# irkit_periph_lightFilter_v03.net
KiCad netlist of a schematic drawn in EAGLE
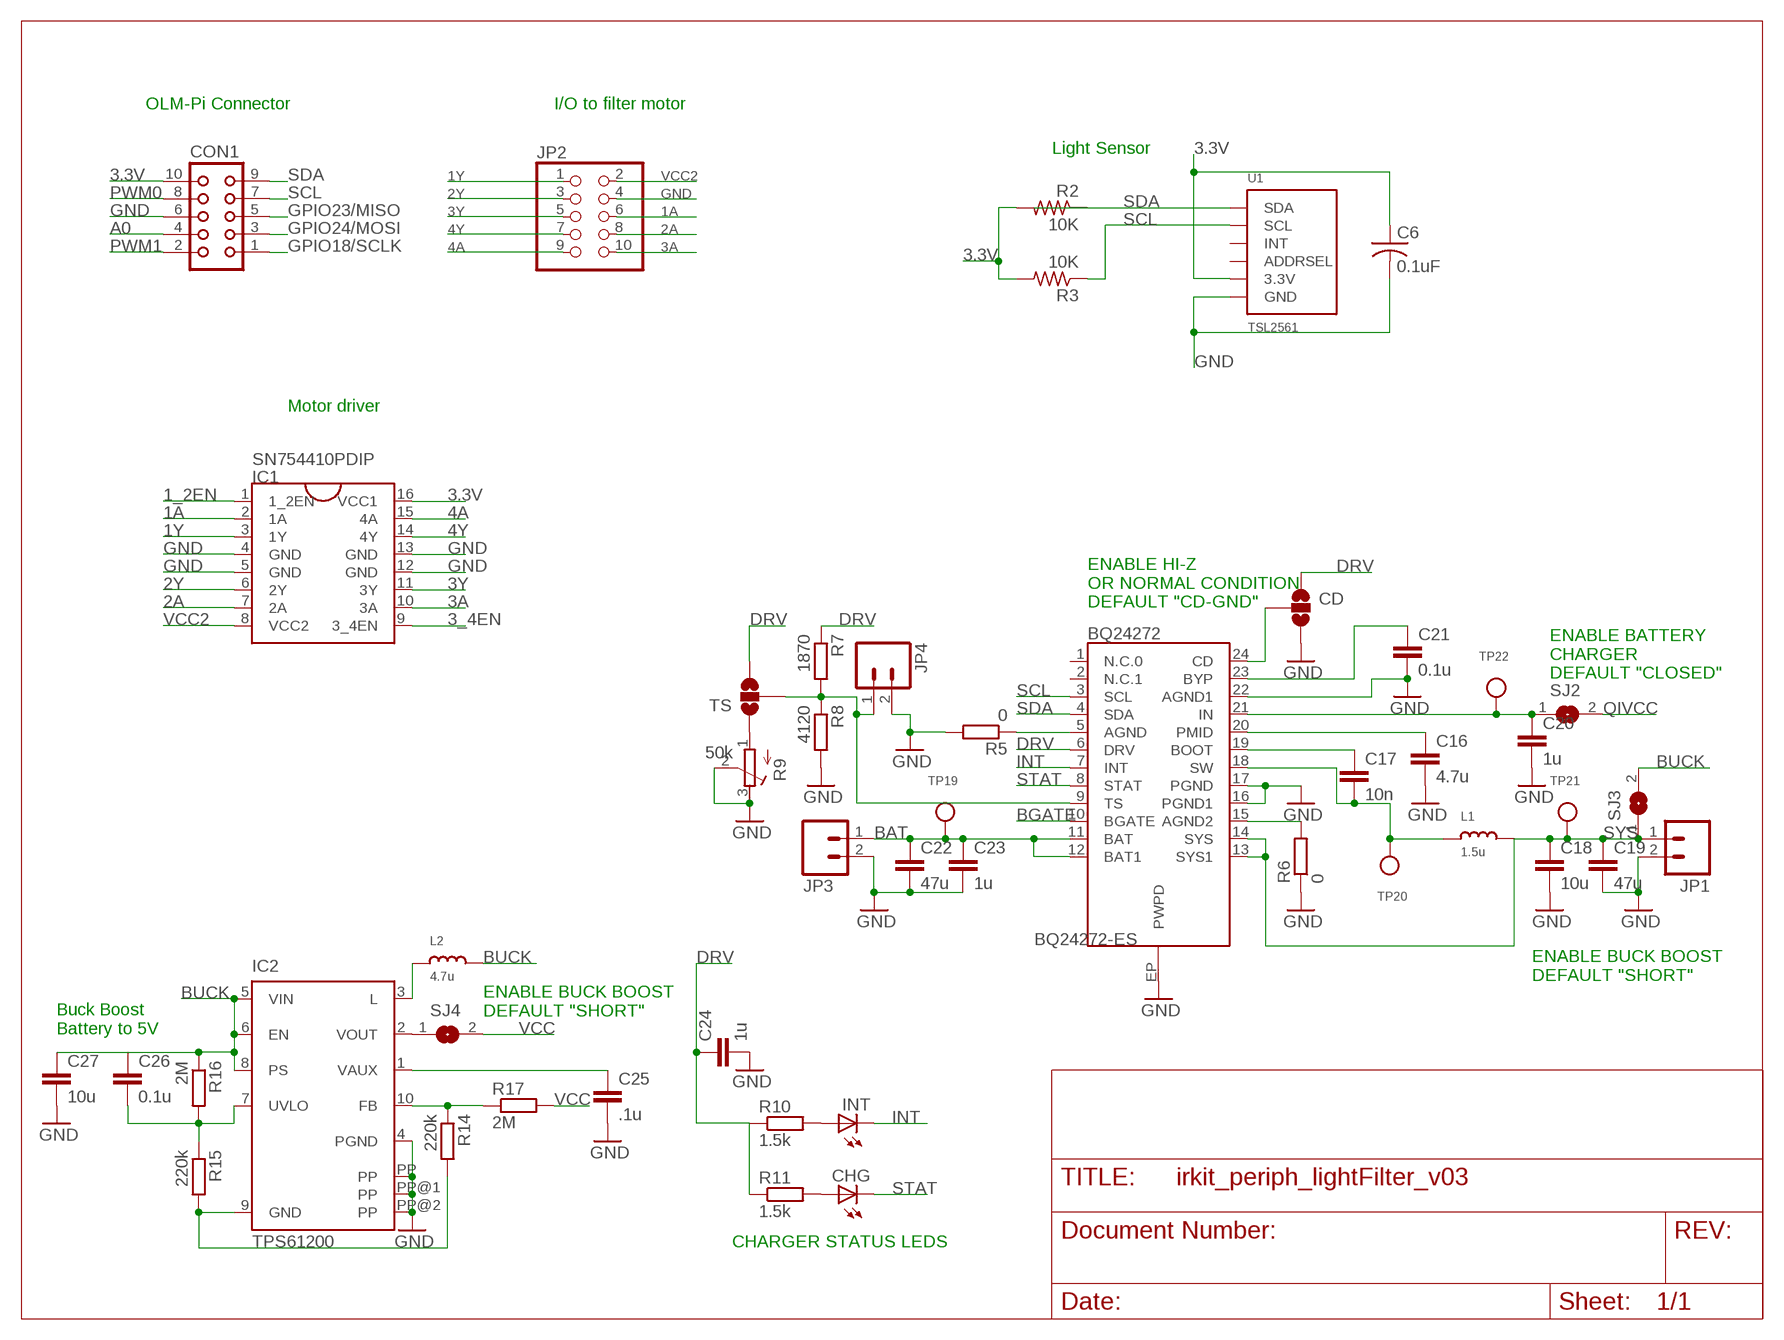
[diagram p0: schematic, sheet 1]

(export (version "E")
  (design (tool "Eeschema 10.0.6"))
  (components
    (comp (ref "BQ24272")
      (value "BQ24272-ES")
      (footprint "eagle-import:QFN-24_ALT2")
      (libsource (lib "eagle-import") (part "BQ24272-ES"))
    )
    (comp (ref "C6")
      (value "0.1uF")
      (footprint "eagle-import:C0805")
      (libsource (lib "eagle-import") (part "C-USC0805"))
    )
    (comp (ref "C16")
      (value "4.7u")
      (footprint "eagle-import:C0603K")
      (libsource (lib "eagle-import") (part "C-EUC0603K"))
    )
    (comp (ref "C17")
      (value "10n")
      (footprint "eagle-import:C0603K")
      (libsource (lib "eagle-import") (part "C-EUC0603K"))
    )
    (comp (ref "C18")
      (value "10u")
      (footprint "eagle-import:C0603K")
      (libsource (lib "eagle-import") (part "C-EUC0603K"))
    )
    (comp (ref "C19")
      (value "47u")
      (footprint "eagle-import:C0603K")
      (libsource (lib "eagle-import") (part "C-EUC0603K"))
    )
    (comp (ref "C20")
      (value "1u")
      (footprint "eagle-import:C0603K")
      (libsource (lib "eagle-import") (part "C-EUC0603K"))
    )
    (comp (ref "C21")
      (value "0.1u")
      (footprint "eagle-import:C0603K")
      (libsource (lib "eagle-import") (part "C-EUC0603K"))
    )
    (comp (ref "C22")
      (value "47u")
      (footprint "eagle-import:C0603K")
      (libsource (lib "eagle-import") (part "C-EUC0603K"))
    )
    (comp (ref "C23")
      (value "1u")
      (footprint "eagle-import:C0603K")
      (libsource (lib "eagle-import") (part "C-EUC0603K"))
    )
    (comp (ref "C24")
      (value "1u")
      (footprint "eagle-import:C0603K")
      (libsource (lib "eagle-import") (part "C-EUC0603K"))
    )
    (comp (ref "C25")
      (value ".1u")
      (footprint "eagle-import:C0603K")
      (libsource (lib "eagle-import") (part "C-EUC0603K"))
    )
    (comp (ref "C26")
      (value "0.1u")
      (footprint "eagle-import:C0603K")
      (libsource (lib "eagle-import") (part "C-EUC0603K"))
    )
    (comp (ref "C27")
      (value "10u")
      (footprint "eagle-import:C0603K")
      (libsource (lib "eagle-import") (part "C-EUC0603K"))
    )
    (comp (ref "CD")
      (value "SOLDERJUMPER_2WAYS")
      (footprint "eagle-import:SJ_3")
      (libsource (lib "eagle-import") (part "SOLDERJUMPER_2WAYS"))
    )
    (comp (ref "CHG")
      (value "LEDCHIP-LED0603")
      (footprint "eagle-import:CHIP-LED0603")
      (libsource (lib "eagle-import") (part "LEDCHIP-LED0603"))
    )
    (comp (ref "CON1")
      (value "CON10L")
      (footprint "eagle-import:CON10L")
      (libsource (lib "eagle-import") (part "CON10L"))
    )
    (comp (ref "IC1")
      (value "SN754410PDIP")
      (footprint "eagle-import:DIL16")
      (libsource (lib "eagle-import") (part "SN754410PDIP"))
    )
    (comp (ref "IC2")
      (value "TPS61200")
      (footprint "eagle-import:S-PDSO-N10")
      (fields (field (name "MPN") "TPS61200DRCT"))
      (libsource (lib "eagle-import") (part "TPS61200"))
    )
    (comp (ref "INT")
      (value "LEDCHIP-LED0603")
      (footprint "eagle-import:CHIP-LED0603")
      (libsource (lib "eagle-import") (part "LEDCHIP-LED0603"))
    )
    (comp (ref "JP1")
      (value "M02PTH3")
      (footprint "eagle-import:1X02_LONGPADS")
      (libsource (lib "eagle-import") (part "M02PTH3"))
    )
    (comp (ref "JP2")
      (value "PINHD-2X5")
      (footprint "eagle-import:2X05")
      (libsource (lib "eagle-import") (part "PINHD-2X5"))
    )
    (comp (ref "JP3")
      (value "M02PTH3")
      (footprint "eagle-import:1X02_LONGPADS")
      (libsource (lib "eagle-import") (part "M02PTH3"))
    )
    (comp (ref "JP4")
      (value "M02PTH3")
      (footprint "eagle-import:1X02_LONGPADS")
      (libsource (lib "eagle-import") (part "M02PTH3"))
    )
    (comp (ref "L1")
      (value "1.5u")
      (footprint "eagle-import:INDUCTOR_5X5MM_NR5040_NOTHERMALS")
      (libsource (lib "eagle-import") (part "INDUCTORNR5040"))
    )
    (comp (ref "L2")
      (value "4.7u")
      (footprint "eagle-import:INDUCTOR_5X5MM_NR5040_NOTHERMALS")
      (libsource (lib "eagle-import") (part "INDUCTORNR5040"))
    )
    (comp (ref "R2")
      (value "10K")
      (footprint "eagle-import:R0805")
      (libsource (lib "eagle-import") (part "R-US_R0805"))
    )
    (comp (ref "R3")
      (value "10K")
      (footprint "eagle-import:R0805")
      (libsource (lib "eagle-import") (part "R-US_R0805"))
    )
    (comp (ref "R5")
      (value "0")
      (footprint "eagle-import:R0402")
      (fields (field (name "MPN") "ERJ3EKF3000V"))
      (libsource (lib "eagle-import") (part "R-EU_R0402"))
    )
    (comp (ref "R6")
      (value "0")
      (footprint "eagle-import:R0402")
      (fields (field (name "MPN") "ERJ3EKF3000V"))
      (libsource (lib "eagle-import") (part "R-EU_R0402"))
    )
    (comp (ref "R7")
      (value "1870")
      (footprint "eagle-import:R0402")
      (fields (field (name "MPN") "ERJ3EKF3000V"))
      (libsource (lib "eagle-import") (part "R-EU_R0402"))
    )
    (comp (ref "R8")
      (value "4120")
      (footprint "eagle-import:R0402")
      (fields (field (name "MPN") "ERJ3EKF3000V"))
      (libsource (lib "eagle-import") (part "R-EU_R0402"))
    )
    (comp (ref "R9")
      (value "50k")
      (footprint "eagle-import:RTRIM64Y")
      (libsource (lib "eagle-import") (part "R-TRIMM64Y"))
    )
    (comp (ref "R10")
      (value "1.5k")
      (footprint "eagle-import:R0402")
      (fields (field (name "MPN") "ERJ3EKF3000V"))
      (libsource (lib "eagle-import") (part "R-EU_R0402"))
    )
    (comp (ref "R11")
      (value "1.5k")
      (footprint "eagle-import:R0402")
      (fields (field (name "MPN") "ERJ3EKF3000V"))
      (libsource (lib "eagle-import") (part "R-EU_R0402"))
    )
    (comp (ref "R14")
      (value "220k")
      (footprint "eagle-import:R0402")
      (fields (field (name "MPN") "ERJ3EKF3000V"))
      (libsource (lib "eagle-import") (part "R-EU_R0402"))
    )
    (comp (ref "R15")
      (value "220k")
      (footprint "eagle-import:R0402")
      (fields (field (name "MPN") "ERJ3EKF3000V"))
      (libsource (lib "eagle-import") (part "R-EU_R0402"))
    )
    (comp (ref "R16")
      (value "2M")
      (footprint "eagle-import:R0402")
      (fields (field (name "MPN") "ERJ3EKF3000V"))
      (libsource (lib "eagle-import") (part "R-EU_R0402"))
    )
    (comp (ref "R17")
      (value "2M")
      (footprint "eagle-import:R0402")
      (fields (field (name "MPN") "ERJ3EKF3000V"))
      (libsource (lib "eagle-import") (part "R-EU_R0402"))
    )
    (comp (ref "SJ2") (value "SJ") (footprint "eagle-import:SJ") (libsource (lib "eagle-import") (part "SJ")))
    (comp (ref "SJ3") (value "SJ") (footprint "eagle-import:SJ") (libsource (lib "eagle-import") (part "SJ")))
    (comp (ref "SJ4") (value "SJ") (footprint "eagle-import:SJ") (libsource (lib "eagle-import") (part "SJ")))
    (comp (ref "TP19")
      (value "TESTPOINTROUND1MM")
      (footprint "eagle-import:TESTPOINT_ROUND_1MM")
      (libsource (lib "eagle-import") (part "TESTPOINTROUND1MM"))
    )
    (comp (ref "TP20")
      (value "TESTPOINTROUND1MM")
      (footprint "eagle-import:TESTPOINT_ROUND_1MM")
      (libsource (lib "eagle-import") (part "TESTPOINTROUND1MM"))
    )
    (comp (ref "TP21")
      (value "TESTPOINTROUND1MM")
      (footprint "eagle-import:TESTPOINT_ROUND_1MM")
      (libsource (lib "eagle-import") (part "TESTPOINTROUND1MM"))
    )
    (comp (ref "TP22")
      (value "TESTPOINTROUND1MM")
      (footprint "eagle-import:TESTPOINT_ROUND_1MM")
      (libsource (lib "eagle-import") (part "TESTPOINTROUND1MM"))
    )
    (comp (ref "TS")
      (value "SOLDERJUMPER_2WAYS")
      (footprint "eagle-import:SJ_3")
      (libsource (lib "eagle-import") (part "SOLDERJUMPER_2WAYS"))
    )
    (comp (ref "U1")
      (value "TSL2561")
      (footprint "eagle-import:TSL2561_FN")
      (libsource (lib "eagle-import") (part "TSL2561"))
    )
  )
  (nets
    (net (code "1") (name "/1A") (class "Default")
      (node (ref "IC1") (pin "2") (pinfunction "1A_2") (pintype "bidirectional"))
      (node (ref "JP2") (pin "6") (pinfunction "6_6") (pintype "passive"))
    )
    (net (code "2") (name "/1Y") (class "Default")
      (node (ref "IC1") (pin "3") (pinfunction "1Y_3") (pintype "bidirectional"))
      (node (ref "JP2") (pin "1") (pinfunction "1_1") (pintype "passive"))
    )
    (net (code "3") (name "/1_2EN") (class "Default")
      (node (ref "IC1") (pin "1") (pinfunction "1_2EN_1") (pintype "bidirectional"))
    )
    (net (code "4") (name "/2A") (class "Default")
      (node (ref "IC1") (pin "7") (pinfunction "2A_7") (pintype "bidirectional"))
      (node (ref "JP2") (pin "8") (pinfunction "8_8") (pintype "passive"))
    )
    (net (code "5") (name "/2Y") (class "Default")
      (node (ref "IC1") (pin "6") (pinfunction "2Y_6") (pintype "bidirectional"))
      (node (ref "JP2") (pin "3") (pinfunction "3_3") (pintype "passive"))
    )
    (net (code "6") (name "/3.3V") (class "Default")
      (node (ref "C6") (pin "1") (pinfunction "1_1") (pintype "passive"))
      (node (ref "CON1") (pin "10") (pinfunction "10_10") (pintype "passive"))
      (node (ref "IC1") (pin "16") (pinfunction "VCC1_16") (pintype "bidirectional"))
      (node (ref "R2") (pin "2") (pinfunction "2_2") (pintype "passive"))
      (node (ref "R3") (pin "2") (pinfunction "2_2") (pintype "passive"))
      (node (ref "U1") (pin "VDD") (pinfunction "3.3V_VDD") (pintype "bidirectional"))
    )
    (net (code "7") (name "/3A") (class "Default")
      (node (ref "IC1") (pin "10") (pinfunction "3A_10") (pintype "bidirectional"))
      (node (ref "JP2") (pin "10") (pinfunction "10_10") (pintype "passive"))
    )
    (net (code "8") (name "/3Y") (class "Default")
      (node (ref "IC1") (pin "11") (pinfunction "3Y_11") (pintype "bidirectional"))
      (node (ref "JP2") (pin "5") (pinfunction "5_5") (pintype "passive"))
    )
    (net (code "9") (name "/3_4EN") (class "Default")
      (node (ref "IC1") (pin "9") (pinfunction "3_4EN_9") (pintype "bidirectional"))
    )
    (net (code "10") (name "/4A") (class "Default")
      (node (ref "IC1") (pin "15") (pinfunction "4A_15") (pintype "bidirectional"))
      (node (ref "JP2") (pin "9") (pinfunction "9_9") (pintype "passive"))
    )
    (net (code "11") (name "/4Y") (class "Default")
      (node (ref "IC1") (pin "14") (pinfunction "4Y_14") (pintype "bidirectional"))
      (node (ref "JP2") (pin "7") (pinfunction "7_7") (pintype "passive"))
    )
    (net (code "12") (name "/A0") (class "Default")
      (node (ref "CON1") (pin "4") (pinfunction "4_4") (pintype "passive"))
    )
    (net (code "13") (name "/BAT") (class "Default")
      (node (ref "BQ24272") (pin "11") (pinfunction "BAT_11") (pintype "bidirectional"))
      (node (ref "BQ24272") (pin "12") (pinfunction "BAT1_12") (pintype "bidirectional"))
      (node (ref "C22") (pin "1") (pinfunction "1_1") (pintype "passive"))
      (node (ref "C23") (pin "1") (pinfunction "1_1") (pintype "passive"))
      (node (ref "JP3") (pin "1") (pinfunction "1_1") (pintype "passive"))
      (node (ref "TP19") (pin "P$1") (pinfunction "P$1_P$1") (pintype "bidirectional"))
    )
    (net (code "14") (name "/BGATE") (class "Default")
      (node (ref "BQ24272") (pin "10") (pinfunction "BGATE_10") (pintype "bidirectional"))
    )
    (net (code "15") (name "/BUCK") (class "Default")
      (node (ref "C26") (pin "1") (pinfunction "1_1") (pintype "passive"))
      (node (ref "C27") (pin "1") (pinfunction "1_1") (pintype "passive"))
      (node (ref "IC2") (pin "5") (pinfunction "VIN_5") (pintype "input"))
      (node (ref "IC2") (pin "6") (pinfunction "EN_6") (pintype "input"))
      (node (ref "IC2") (pin "8") (pinfunction "PS_8") (pintype "input"))
      (node (ref "L2") (pin "P$2") (pinfunction "2_P$2") (pintype "passive"))
      (node (ref "R16") (pin "1") (pinfunction "1_1") (pintype "passive"))
      (node (ref "SJ3") (pin "2") (pinfunction "2_2") (pintype "passive"))
    )
    (net (code "16") (name "/DRV") (class "Default")
      (node (ref "BQ24272") (pin "6") (pinfunction "DRV_6") (pintype "bidirectional"))
      (node (ref "C24") (pin "1") (pinfunction "1_1") (pintype "passive"))
      (node (ref "CD") (pin "1") (pinfunction "1_1") (pintype "passive"))
      (node (ref "R10") (pin "1") (pinfunction "1_1") (pintype "passive"))
      (node (ref "R11") (pin "1") (pinfunction "1_1") (pintype "passive"))
      (node (ref "R7") (pin "1") (pinfunction "1_1") (pintype "passive"))
      (node (ref "TS") (pin "3") (pinfunction "3_3") (pintype "passive"))
    )
    (net (code "17") (name "/GPIO18{slash}SCLK") (class "Default")
      (node (ref "CON1") (pin "1") (pinfunction "1_1") (pintype "passive"))
    )
    (net (code "18") (name "/GPIO23{slash}MISO") (class "Default")
      (node (ref "CON1") (pin "5") (pinfunction "5_5") (pintype "passive"))
    )
    (net (code "19") (name "/GPIO24{slash}MOSI") (class "Default")
      (node (ref "CON1") (pin "3") (pinfunction "3_3") (pintype "passive"))
    )
    (net (code "20") (name "/INT") (class "Default")
      (node (ref "BQ24272") (pin "7") (pinfunction "INT_7") (pintype "bidirectional"))
      (node (ref "INT") (pin "C") (pinfunction "C_C") (pintype "passive"))
    )
    (net (code "21") (name "/PWM0") (class "Default")
      (node (ref "CON1") (pin "8") (pinfunction "8_8") (pintype "passive"))
    )
    (net (code "22") (name "/PWM1") (class "Default")
      (node (ref "CON1") (pin "2") (pinfunction "2_2") (pintype "passive"))
    )
    (net (code "23") (name "/QIVCC") (class "Default")
      (node (ref "SJ2") (pin "2") (pinfunction "2_2") (pintype "passive"))
    )
    (net (code "24") (name "/SCL") (class "Default")
      (node (ref "BQ24272") (pin "3") (pinfunction "SCL_3") (pintype "bidirectional"))
      (node (ref "CON1") (pin "7") (pinfunction "7_7") (pintype "passive"))
      (node (ref "R3") (pin "1") (pinfunction "1_1") (pintype "passive"))
      (node (ref "U1") (pin "CLK") (pinfunction "SCL_CLK") (pintype "bidirectional"))
    )
    (net (code "25") (name "/SDA") (class "Default")
      (node (ref "BQ24272") (pin "4") (pinfunction "SDA_4") (pintype "bidirectional"))
      (node (ref "CON1") (pin "9") (pinfunction "9_9") (pintype "passive"))
      (node (ref "R2") (pin "1") (pinfunction "1_1") (pintype "passive"))
      (node (ref "U1") (pin "DATA") (pinfunction "SDA_DATA") (pintype "bidirectional"))
    )
    (net (code "26") (name "/STAT") (class "Default")
      (node (ref "BQ24272") (pin "8") (pinfunction "STAT_8") (pintype "bidirectional"))
      (node (ref "CHG") (pin "C") (pinfunction "C_C") (pintype "passive"))
    )
    (net (code "27") (name "/SYS") (class "Default")
      (node (ref "BQ24272") (pin "13") (pinfunction "SYS1_13") (pintype "bidirectional"))
      (node (ref "BQ24272") (pin "14") (pinfunction "SYS_14") (pintype "bidirectional"))
      (node (ref "C18") (pin "1") (pinfunction "1_1") (pintype "passive"))
      (node (ref "C19") (pin "1") (pinfunction "1_1") (pintype "passive"))
      (node (ref "JP1") (pin "1") (pinfunction "1_1") (pintype "passive"))
      (node (ref "L1") (pin "P$2") (pinfunction "2_P$2") (pintype "passive"))
      (node (ref "SJ3") (pin "1") (pinfunction "1_1") (pintype "passive"))
      (node (ref "TP21") (pin "P$1") (pinfunction "P$1_P$1") (pintype "bidirectional"))
    )
    (net (code "28") (name "/VCC") (class "Default")
      (node (ref "R17") (pin "2") (pinfunction "2_2") (pintype "passive"))
      (node (ref "SJ4") (pin "2") (pinfunction "2_2") (pintype "passive"))
    )
    (net (code "29") (name "/VCC2") (class "Default")
      (node (ref "IC1") (pin "8") (pinfunction "VCC2_8") (pintype "bidirectional"))
      (node (ref "JP2") (pin "2") (pinfunction "2_2") (pintype "passive"))
    )
    (net (code "30") (name "GND") (class "Default")
      (node (ref "BQ24272") (pin "16") (pinfunction "PGND1_16") (pintype "bidirectional"))
      (node (ref "BQ24272") (pin "17") (pinfunction "PGND_17") (pintype "bidirectional"))
      (node (ref "BQ24272") (pin "22") (pinfunction "AGND1_22") (pintype "bidirectional"))
      (node (ref "BQ24272") (pin "EP") (pinfunction "PWPD_EP") (pintype "bidirectional"))
      (node (ref "C16") (pin "2") (pinfunction "2_2") (pintype "passive"))
      (node (ref "C18") (pin "2") (pinfunction "2_2") (pintype "passive"))
      (node (ref "C19") (pin "2") (pinfunction "2_2") (pintype "passive"))
      (node (ref "C20") (pin "2") (pinfunction "2_2") (pintype "passive"))
      (node (ref "C21") (pin "2") (pinfunction "2_2") (pintype "passive"))
      (node (ref "C22") (pin "2") (pinfunction "2_2") (pintype "passive"))
      (node (ref "C23") (pin "2") (pinfunction "2_2") (pintype "passive"))
      (node (ref "C24") (pin "2") (pinfunction "2_2") (pintype "passive"))
      (node (ref "C25") (pin "2") (pinfunction "2_2") (pintype "passive"))
      (node (ref "C27") (pin "2") (pinfunction "2_2") (pintype "passive"))
      (node (ref "C6") (pin "2") (pinfunction "2_2") (pintype "passive"))
      (node (ref "CD") (pin "3") (pinfunction "3_3") (pintype "passive"))
      (node (ref "CON1") (pin "6") (pinfunction "6_6") (pintype "passive"))
      (node (ref "IC1") (pin "12") (pinfunction "GND_12") (pintype "bidirectional"))
      (node (ref "IC1") (pin "13") (pinfunction "GND_13") (pintype "bidirectional"))
      (node (ref "IC1") (pin "4") (pinfunction "GND_4") (pintype "bidirectional"))
      (node (ref "IC1") (pin "5") (pinfunction "GND_5") (pintype "bidirectional"))
      (node (ref "IC2") (pin "4") (pinfunction "PGND_4") (pintype "power_in"))
      (node (ref "IC2") (pin "PP") (pinfunction "PP_PP") (pintype "power_in"))
      (node (ref "IC2") (pin "PP@1") (pinfunction "PP_PP@1") (pintype "power_in"))
      (node (ref "IC2") (pin "PP@2") (pinfunction "PP_PP@2") (pintype "power_in"))
      (node (ref "JP1") (pin "2") (pinfunction "2_2") (pintype "passive"))
      (node (ref "JP2") (pin "4") (pinfunction "4_4") (pintype "passive"))
      (node (ref "JP3") (pin "2") (pinfunction "2_2") (pintype "passive"))
      (node (ref "JP4") (pin "2") (pinfunction "2_2") (pintype "passive"))
      (node (ref "R5") (pin "2") (pinfunction "2_2") (pintype "passive"))
      (node (ref "R6") (pin "1") (pinfunction "1_1") (pintype "passive"))
      (node (ref "R8") (pin "2") (pinfunction "2_2") (pintype "passive"))
      (node (ref "R9") (pin "2") (pinfunction "S_2") (pintype "passive"))
      (node (ref "R9") (pin "3") (pinfunction "E_3") (pintype "passive"))
      (node (ref "U1") (pin "VSS") (pinfunction "GND_VSS") (pintype "bidirectional"))
    )
    (net (code "31") (name "Net-(BQ24272-AGND)") (class "Default")
      (node (ref "BQ24272") (pin "5") (pinfunction "AGND_5") (pintype "bidirectional"))
      (node (ref "R5") (pin "1") (pinfunction "1_1") (pintype "passive"))
    )
    (net (code "32") (name "Net-(BQ24272-AGND2)") (class "Default")
      (node (ref "BQ24272") (pin "15") (pinfunction "AGND2_15") (pintype "bidirectional"))
      (node (ref "R6") (pin "2") (pinfunction "2_2") (pintype "passive"))
    )
    (net (code "33") (name "Net-(BQ24272-BOOT)") (class "Default")
      (node (ref "BQ24272") (pin "19") (pinfunction "BOOT_19") (pintype "bidirectional"))
      (node (ref "C17") (pin "1") (pinfunction "1_1") (pintype "passive"))
    )
    (net (code "34") (name "Net-(BQ24272-BYP)") (class "Default")
      (node (ref "BQ24272") (pin "23") (pinfunction "BYP_23") (pintype "bidirectional"))
      (node (ref "C21") (pin "1") (pinfunction "1_1") (pintype "passive"))
    )
    (net (code "35") (name "Net-(BQ24272-CD)") (class "Default")
      (node (ref "BQ24272") (pin "24") (pinfunction "CD_24") (pintype "bidirectional"))
      (node (ref "CD") (pin "2") (pinfunction "2_2") (pintype "passive"))
    )
    (net (code "36") (name "Net-(BQ24272-IN)") (class "Default")
      (node (ref "BQ24272") (pin "21") (pinfunction "IN_21") (pintype "bidirectional"))
      (node (ref "C20") (pin "1") (pinfunction "1_1") (pintype "passive"))
      (node (ref "SJ2") (pin "1") (pinfunction "1_1") (pintype "passive"))
      (node (ref "TP22") (pin "P$1") (pinfunction "P$1_P$1") (pintype "bidirectional"))
    )
    (net (code "37") (name "Net-(BQ24272-PMID)") (class "Default")
      (node (ref "BQ24272") (pin "20") (pinfunction "PMID_20") (pintype "bidirectional"))
      (node (ref "C16") (pin "1") (pinfunction "1_1") (pintype "passive"))
    )
    (net (code "38") (name "Net-(BQ24272-SW)") (class "Default")
      (node (ref "BQ24272") (pin "18") (pinfunction "SW_18") (pintype "bidirectional"))
      (node (ref "C17") (pin "2") (pinfunction "2_2") (pintype "passive"))
      (node (ref "L1") (pin "P$1") (pinfunction "1_P$1") (pintype "passive"))
      (node (ref "TP20") (pin "P$1") (pinfunction "P$1_P$1") (pintype "bidirectional"))
    )
    (net (code "39") (name "Net-(BQ24272-TS)") (class "Default")
      (node (ref "BQ24272") (pin "9") (pinfunction "TS_9") (pintype "bidirectional"))
      (node (ref "JP4") (pin "1") (pinfunction "1_1") (pintype "passive"))
      (node (ref "R7") (pin "2") (pinfunction "2_2") (pintype "passive"))
      (node (ref "R8") (pin "1") (pinfunction "1_1") (pintype "passive"))
      (node (ref "TS") (pin "2") (pinfunction "2_2") (pintype "passive"))
    )
    (net (code "40") (name "Net-(CHG-PadA)") (class "Default")
      (node (ref "CHG") (pin "A") (pinfunction "A_A") (pintype "passive"))
      (node (ref "R11") (pin "2") (pinfunction "2_2") (pintype "passive"))
    )
    (net (code "41") (name "Net-(IC2-FB)") (class "Default")
      (node (ref "IC2") (pin "10") (pinfunction "FB_10") (pintype "input"))
      (node (ref "R14") (pin "1") (pinfunction "1_1") (pintype "passive"))
      (node (ref "R17") (pin "1") (pinfunction "1_1") (pintype "passive"))
    )
    (net (code "42") (name "Net-(IC2-GND)") (class "Default")
      (node (ref "IC2") (pin "9") (pinfunction "GND_9") (pintype "power_in"))
      (node (ref "R14") (pin "2") (pinfunction "2_2") (pintype "passive"))
      (node (ref "R15") (pin "2") (pinfunction "2_2") (pintype "passive"))
    )
    (net (code "43") (name "Net-(IC2-L)") (class "Default")
      (node (ref "IC2") (pin "3") (pinfunction "L_3") (pintype "input"))
      (node (ref "L2") (pin "P$1") (pinfunction "1_P$1") (pintype "passive"))
    )
    (net (code "44") (name "Net-(IC2-UVLO)") (class "Default")
      (node (ref "C26") (pin "2") (pinfunction "2_2") (pintype "passive"))
      (node (ref "IC2") (pin "7") (pinfunction "UVLO_7") (pintype "input"))
      (node (ref "R15") (pin "1") (pinfunction "1_1") (pintype "passive"))
      (node (ref "R16") (pin "2") (pinfunction "2_2") (pintype "passive"))
    )
    (net (code "45") (name "Net-(IC2-VAUX)") (class "Default")
      (node (ref "C25") (pin "1") (pinfunction "1_1") (pintype "passive"))
      (node (ref "IC2") (pin "1") (pinfunction "VAUX_1") (pintype "bidirectional"))
    )
    (net (code "46") (name "Net-(IC2-VOUT)") (class "Default")
      (node (ref "IC2") (pin "2") (pinfunction "VOUT_2") (pintype "passive"))
      (node (ref "SJ4") (pin "1") (pinfunction "1_1") (pintype "passive"))
    )
    (net (code "47") (name "Net-(INT-PadA)") (class "Default")
      (node (ref "INT") (pin "A") (pinfunction "A_A") (pintype "passive"))
      (node (ref "R10") (pin "2") (pinfunction "2_2") (pintype "passive"))
    )
    (net (code "48") (name "Net-(R9-A)") (class "Default")
      (node (ref "R9") (pin "1") (pinfunction "A_1") (pintype "passive"))
      (node (ref "TS") (pin "1") (pinfunction "1_1") (pintype "passive"))
    )
    (net (code "49") (name "unconnected-(BQ24272-N.C.0-Pad1)") (class "Default")
      (node (ref "BQ24272") (pin "1") (pinfunction "N.C.0_1") (pintype "bidirectional"))
    )
    (net (code "50") (name "unconnected-(BQ24272-N.C.1-Pad2)") (class "Default")
      (node (ref "BQ24272") (pin "2") (pinfunction "N.C.1_2") (pintype "bidirectional"))
    )
    (net (code "51") (name "unconnected-(U1-ADDRSEL-PadADR)") (class "Default")
      (node (ref "U1") (pin "ADR") (pinfunction "ADDRSEL_ADR") (pintype "bidirectional"))
    )
    (net (code "52") (name "unconnected-(U1-PadINT)") (class "Default")
      (node (ref "U1") (pin "INT") (pinfunction "INT_INT") (pintype "bidirectional"))
    )
  )
)
